# lazurite_ble_cs75.net
KiCad netlist of a schematic drawn in EAGLE
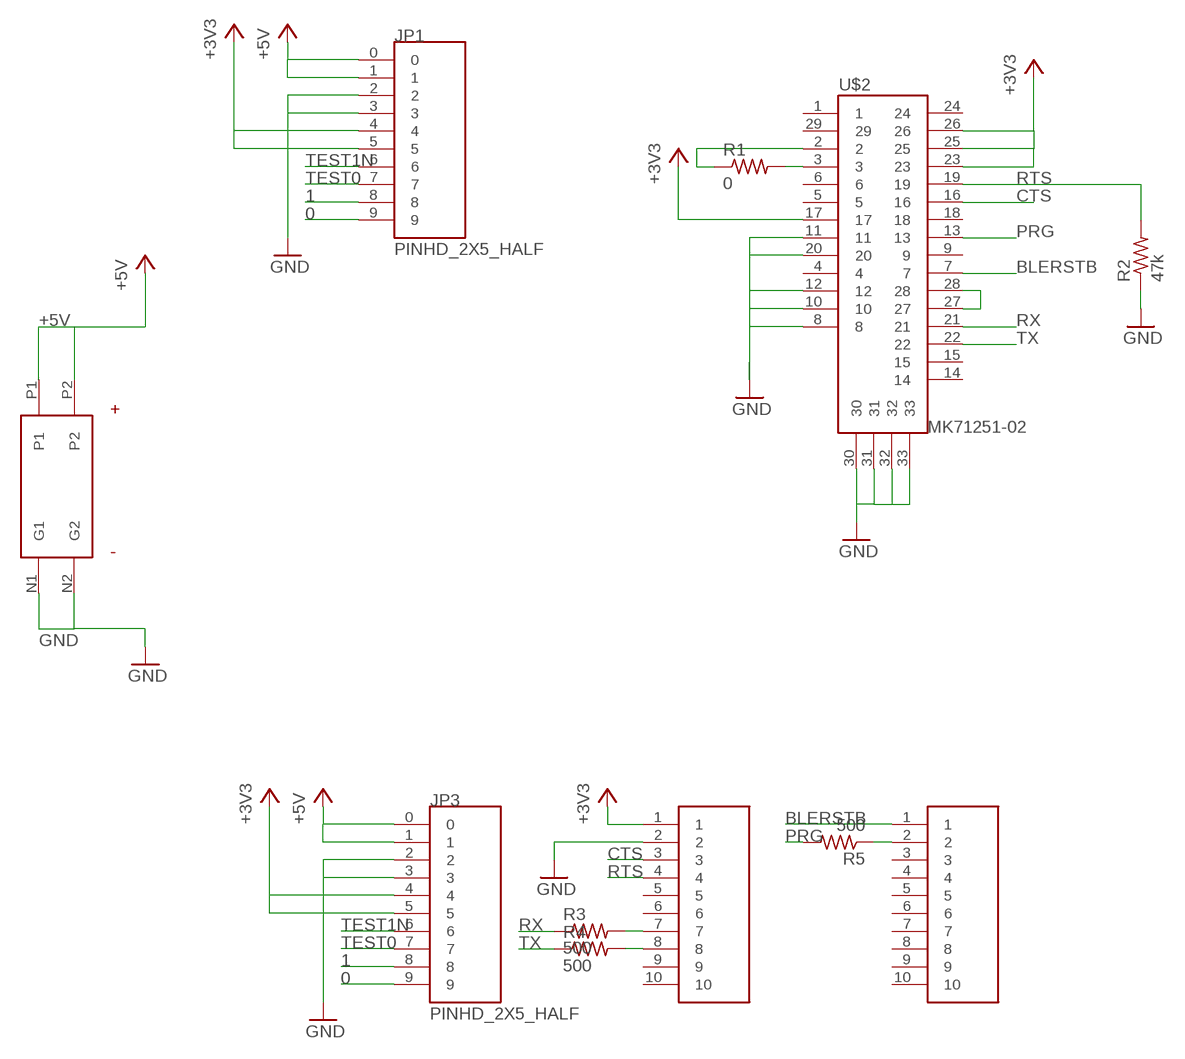
[diagram p0: schematic, sheet 1]

(export (version "E")
  (design (tool "Eeschema 10.0.6"))
  (components
    (comp (ref "JP1")
      (value "PINHD_2X5_HALF")
      (footprint "eagle-import:PINHD_2X5_HALF")
      (libsource (lib "eagle-import") (part "PINHD_2X5_HALF"))
    )
    (comp (ref "JP3")
      (value "PINHD_2X5_HALF")
      (footprint "eagle-import:PINHD_2X5_HALF")
      (libsource (lib "eagle-import") (part "PINHD_2X5_HALF"))
    )
    (comp (ref "R1")
      (value "0")
      (footprint "eagle-import:R0402")
      (libsource (lib "eagle-import") (part "R-US_R0402"))
    )
    (comp (ref "R2")
      (value "47k")
      (footprint "eagle-import:R0402")
      (libsource (lib "eagle-import") (part "R-US_R0402"))
    )
    (comp (ref "R3")
      (value "500")
      (footprint "eagle-import:R0402")
      (libsource (lib "eagle-import") (part "R-US_R0402"))
    )
    (comp (ref "R4")
      (value "500")
      (footprint "eagle-import:R0402")
      (libsource (lib "eagle-import") (part "R-US_R0402"))
    )
    (comp (ref "R5")
      (value "500")
      (footprint "eagle-import:R0402")
      (libsource (lib "eagle-import") (part "R-US_R0402"))
    )
    (comp (ref "U$1")
      (value "TAKACHI_CS75_BATTERY")
      (footprint "eagle-import:TAKACHI_CS75_BATTERY")
      (libsource (lib "eagle-import") (part "TAKACHI_CS75_BATTERY"))
    )
    (comp (ref "U$2")
      (value "MK71251-02")
      (footprint "eagle-import:MK71251-02")
      (libsource (lib "eagle-import") (part "MK71251-02"))
    )
    (comp (ref "U$3")
      (value "PINHD_1_10_HALF")
      (footprint "eagle-import:PINHD_1X10_HALF")
      (libsource (lib "eagle-import") (part "PINHD_1_10_HALF"))
    )
    (comp (ref "U$4")
      (value "PINHD_1_10_HALF")
      (footprint "eagle-import:PINHD_1X10_HALF")
      (libsource (lib "eagle-import") (part "PINHD_1_10_HALF"))
    )
  )
  (nets
    (net (code "1") (name "+3V3") (class "Default")
      (node (ref "JP1") (pin "4") (pinfunction "4_4") (pintype "bidirectional"))
      (node (ref "JP1") (pin "5") (pinfunction "5_5") (pintype "bidirectional"))
      (node (ref "JP3") (pin "4") (pinfunction "4_4") (pintype "bidirectional"))
      (node (ref "JP3") (pin "5") (pinfunction "5_5") (pintype "bidirectional"))
      (node (ref "U$2") (pin "17") (pinfunction "17_17") (pintype "power_in"))
      (node (ref "U$2") (pin "23") (pinfunction "23_23") (pintype "bidirectional"))
      (node (ref "U$2") (pin "25") (pinfunction "25_25") (pintype "bidirectional"))
      (node (ref "U$2") (pin "26") (pinfunction "26_26") (pintype "bidirectional"))
      (node (ref "U$3") (pin "1") (pinfunction "1_1") (pintype "bidirectional"))
    )
    (net (code "2") (name "+5V") (class "Default")
      (node (ref "JP1") (pin "0") (pinfunction "0_0") (pintype "bidirectional"))
      (node (ref "JP1") (pin "1") (pinfunction "1_1") (pintype "bidirectional"))
      (node (ref "JP3") (pin "0") (pinfunction "0_0") (pintype "bidirectional"))
      (node (ref "JP3") (pin "1") (pinfunction "1_1") (pintype "bidirectional"))
      (node (ref "U$1") (pin "P1") (pinfunction "P1_P1") (pintype "power_in"))
      (node (ref "U$1") (pin "P2") (pinfunction "P2_P2") (pintype "power_in"))
    )
    (net (code "3") (name "/0") (class "Default")
      (node (ref "JP1") (pin "9") (pinfunction "9_9") (pintype "bidirectional"))
      (node (ref "JP3") (pin "9") (pinfunction "9_9") (pintype "bidirectional"))
    )
    (net (code "4") (name "/1") (class "Default")
      (node (ref "JP1") (pin "8") (pinfunction "8_8") (pintype "bidirectional"))
      (node (ref "JP3") (pin "8") (pinfunction "8_8") (pintype "bidirectional"))
    )
    (net (code "5") (name "/BLERSTB") (class "Default")
      (node (ref "U$2") (pin "7") (pinfunction "7_7") (pintype "input"))
      (node (ref "U$4") (pin "1") (pinfunction "1_1") (pintype "bidirectional"))
    )
    (net (code "6") (name "/CTS") (class "Default")
      (node (ref "U$2") (pin "16") (pinfunction "16_16") (pintype "bidirectional"))
      (node (ref "U$3") (pin "3") (pinfunction "3_3") (pintype "bidirectional"))
    )
    (net (code "7") (name "/PRG") (class "Default")
      (node (ref "R5") (pin "2") (pinfunction "2_2") (pintype "passive"))
      (node (ref "U$2") (pin "13") (pinfunction "13_13") (pintype "bidirectional"))
    )
    (net (code "8") (name "/RTS") (class "Default")
      (node (ref "R2") (pin "2") (pinfunction "2_2") (pintype "passive"))
      (node (ref "U$2") (pin "19") (pinfunction "19_19") (pintype "input"))
      (node (ref "U$3") (pin "4") (pinfunction "4_4") (pintype "bidirectional"))
    )
    (net (code "9") (name "/RX") (class "Default")
      (node (ref "R3") (pin "1") (pinfunction "1_1") (pintype "passive"))
      (node (ref "U$2") (pin "21") (pinfunction "21_21") (pintype "bidirectional"))
    )
    (net (code "10") (name "/TEST0") (class "Default")
      (node (ref "JP1") (pin "7") (pinfunction "7_7") (pintype "bidirectional"))
      (node (ref "JP3") (pin "7") (pinfunction "7_7") (pintype "bidirectional"))
    )
    (net (code "11") (name "/TEST1N") (class "Default")
      (node (ref "JP1") (pin "6") (pinfunction "6_6") (pintype "bidirectional"))
      (node (ref "JP3") (pin "6") (pinfunction "6_6") (pintype "bidirectional"))
    )
    (net (code "12") (name "/TX") (class "Default")
      (node (ref "R4") (pin "1") (pinfunction "1_1") (pintype "passive"))
      (node (ref "U$2") (pin "22") (pinfunction "22_22") (pintype "bidirectional"))
    )
    (net (code "13") (name "GND") (class "Default")
      (node (ref "JP1") (pin "2") (pinfunction "2_2") (pintype "bidirectional"))
      (node (ref "JP1") (pin "3") (pinfunction "3_3") (pintype "bidirectional"))
      (node (ref "JP3") (pin "2") (pinfunction "2_2") (pintype "bidirectional"))
      (node (ref "JP3") (pin "3") (pinfunction "3_3") (pintype "bidirectional"))
      (node (ref "R2") (pin "1") (pinfunction "1_1") (pintype "passive"))
      (node (ref "U$1") (pin "N1") (pinfunction "G1_N1") (pintype "power_in"))
      (node (ref "U$1") (pin "N2") (pinfunction "G2_N2") (pintype "power_in"))
      (node (ref "U$2") (pin "10") (pinfunction "10_10") (pintype "input"))
      (node (ref "U$2") (pin "11") (pinfunction "11_11") (pintype "bidirectional"))
      (node (ref "U$2") (pin "12") (pinfunction "12_12") (pintype "input"))
      (node (ref "U$2") (pin "20") (pinfunction "20_20") (pintype "bidirectional"))
      (node (ref "U$2") (pin "30") (pinfunction "30_30") (pintype "power_in"))
      (node (ref "U$2") (pin "31") (pinfunction "31_31") (pintype "power_in"))
      (node (ref "U$2") (pin "32") (pinfunction "32_32") (pintype "power_in"))
      (node (ref "U$2") (pin "33") (pinfunction "33_33") (pintype "power_in"))
      (node (ref "U$2") (pin "8") (pinfunction "8_8") (pintype "input"))
      (node (ref "U$3") (pin "2") (pinfunction "2_2") (pintype "bidirectional"))
    )
    (net (code "14") (name "Net-(R1-Pad1)") (class "Default")
      (node (ref "R1") (pin "1") (pinfunction "1_1") (pintype "passive"))
      (node (ref "U$2") (pin "2") (pinfunction "2_2") (pintype "input"))
    )
    (net (code "15") (name "Net-(R1-Pad2)") (class "Default")
      (node (ref "R1") (pin "2") (pinfunction "2_2") (pintype "passive"))
      (node (ref "U$2") (pin "3") (pinfunction "3_3") (pintype "bidirectional"))
    )
    (net (code "16") (name "Net-(R3-Pad2)") (class "Default")
      (node (ref "R3") (pin "2") (pinfunction "2_2") (pintype "passive"))
      (node (ref "U$3") (pin "7") (pinfunction "7_7") (pintype "bidirectional"))
    )
    (net (code "17") (name "Net-(R4-Pad2)") (class "Default")
      (node (ref "R4") (pin "2") (pinfunction "2_2") (pintype "passive"))
      (node (ref "U$3") (pin "8") (pinfunction "8_8") (pintype "bidirectional"))
    )
    (net (code "18") (name "Net-(R5-Pad1)") (class "Default")
      (node (ref "R5") (pin "1") (pinfunction "1_1") (pintype "passive"))
      (node (ref "U$4") (pin "2") (pinfunction "2_2") (pintype "bidirectional"))
    )
    (net (code "19") (name "Net-(U$2-Pad27)") (class "Default")
      (node (ref "U$2") (pin "27") (pinfunction "27_27") (pintype "bidirectional"))
      (node (ref "U$2") (pin "28") (pinfunction "28_28") (pintype "bidirectional"))
    )
    (net (code "20") (name "unconnected-(U$2-Pad1)") (class "Default")
      (node (ref "U$2") (pin "1") (pinfunction "1_1") (pintype "no_connect"))
    )
    (net (code "21") (name "unconnected-(U$2-Pad4)") (class "Default")
      (node (ref "U$2") (pin "4") (pinfunction "4_4") (pintype "bidirectional"))
    )
    (net (code "22") (name "unconnected-(U$2-Pad5)") (class "Default")
      (node (ref "U$2") (pin "5") (pinfunction "5_5") (pintype "bidirectional"))
    )
    (net (code "23") (name "unconnected-(U$2-Pad6)") (class "Default")
      (node (ref "U$2") (pin "6") (pinfunction "6_6") (pintype "bidirectional"))
    )
    (net (code "24") (name "unconnected-(U$2-Pad9)") (class "Default")
      (node (ref "U$2") (pin "9") (pinfunction "9_9") (pintype "bidirectional"))
    )
    (net (code "25") (name "unconnected-(U$2-Pad14)") (class "Default")
      (node (ref "U$2") (pin "14") (pinfunction "14_14") (pintype "bidirectional"))
    )
    (net (code "26") (name "unconnected-(U$2-Pad15)") (class "Default")
      (node (ref "U$2") (pin "15") (pinfunction "15_15") (pintype "bidirectional"))
    )
    (net (code "27") (name "unconnected-(U$2-Pad18)") (class "Default")
      (node (ref "U$2") (pin "18") (pinfunction "18_18") (pintype "bidirectional"))
    )
    (net (code "28") (name "unconnected-(U$2-Pad24)") (class "Default")
      (node (ref "U$2") (pin "24") (pinfunction "24_24") (pintype "bidirectional"))
    )
    (net (code "29") (name "unconnected-(U$2-Pad29)") (class "Default")
      (node (ref "U$2") (pin "29") (pinfunction "29_29") (pintype "no_connect"))
    )
    (net (code "30") (name "unconnected-(U$3-Pad5)") (class "Default")
      (node (ref "U$3") (pin "5") (pinfunction "5_5") (pintype "bidirectional"))
    )
    (net (code "31") (name "unconnected-(U$3-Pad6)") (class "Default")
      (node (ref "U$3") (pin "6") (pinfunction "6_6") (pintype "bidirectional"))
    )
    (net (code "32") (name "unconnected-(U$3-Pad9)") (class "Default")
      (node (ref "U$3") (pin "9") (pinfunction "9_9") (pintype "bidirectional"))
    )
    (net (code "33") (name "unconnected-(U$3-Pad10)") (class "Default")
      (node (ref "U$3") (pin "10") (pinfunction "10_10") (pintype "bidirectional"))
    )
    (net (code "34") (name "unconnected-(U$4-Pad3)") (class "Default")
      (node (ref "U$4") (pin "3") (pinfunction "3_3") (pintype "bidirectional"))
    )
    (net (code "35") (name "unconnected-(U$4-Pad4)") (class "Default")
      (node (ref "U$4") (pin "4") (pinfunction "4_4") (pintype "bidirectional"))
    )
    (net (code "36") (name "unconnected-(U$4-Pad5)") (class "Default")
      (node (ref "U$4") (pin "5") (pinfunction "5_5") (pintype "bidirectional"))
    )
    (net (code "37") (name "unconnected-(U$4-Pad6)") (class "Default")
      (node (ref "U$4") (pin "6") (pinfunction "6_6") (pintype "bidirectional"))
    )
    (net (code "38") (name "unconnected-(U$4-Pad7)") (class "Default")
      (node (ref "U$4") (pin "7") (pinfunction "7_7") (pintype "bidirectional"))
    )
    (net (code "39") (name "unconnected-(U$4-Pad8)") (class "Default")
      (node (ref "U$4") (pin "8") (pinfunction "8_8") (pintype "bidirectional"))
    )
    (net (code "40") (name "unconnected-(U$4-Pad9)") (class "Default")
      (node (ref "U$4") (pin "9") (pinfunction "9_9") (pintype "bidirectional"))
    )
    (net (code "41") (name "unconnected-(U$4-Pad10)") (class "Default")
      (node (ref "U$4") (pin "10") (pinfunction "10_10") (pintype "bidirectional"))
    )
  )
)
